# Receiver.net
KiCad netlist of a schematic drawn in EAGLE
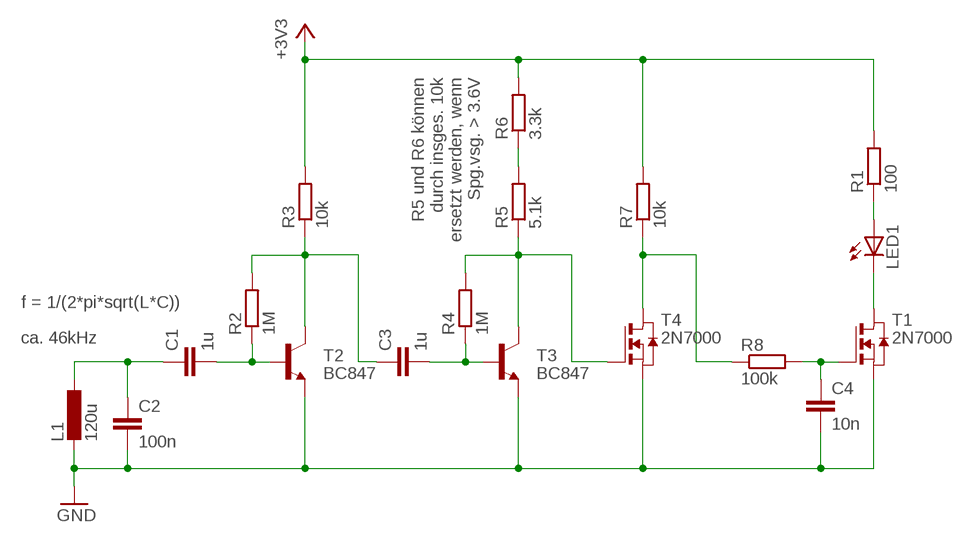
[diagram p0: schematic, sheet 1]

(export (version "E")
  (design (tool "Eeschema 10.0.6"))
  (components
    (comp (ref "C1")
      (value "1u")
      (footprint "eagle-import:C0603")
      (libsource (lib "eagle-import") (part "C-EUC0603"))
    )
    (comp (ref "C2")
      (value "100n")
      (footprint "eagle-import:C0603")
      (libsource (lib "eagle-import") (part "C-EUC0603"))
    )
    (comp (ref "C3")
      (value "1u")
      (footprint "eagle-import:C0603")
      (libsource (lib "eagle-import") (part "C-EUC0603"))
    )
    (comp (ref "C4")
      (value "10n")
      (footprint "eagle-import:C0603")
      (libsource (lib "eagle-import") (part "C-EUC0603"))
    )
    (comp (ref "L1")
      (value "120u")
      (footprint "eagle-import:L1812")
      (libsource (lib "eagle-import") (part "L-EUL1812"))
    )
    (comp (ref "LED1")
      (value "LEDCHIPLED_0603")
      (footprint "eagle-import:CHIPLED_0603")
      (libsource (lib "eagle-import") (part "LEDCHIPLED_0603"))
    )
    (comp (ref "R1")
      (value "100")
      (footprint "eagle-import:R0603")
      (libsource (lib "eagle-import") (part "R-EU_R0603"))
    )
    (comp (ref "R2")
      (value "1M")
      (footprint "eagle-import:R0603")
      (libsource (lib "eagle-import") (part "R-EU_R0603"))
    )
    (comp (ref "R3")
      (value "10k")
      (footprint "eagle-import:R0603")
      (libsource (lib "eagle-import") (part "R-EU_R0603"))
    )
    (comp (ref "R4")
      (value "1M")
      (footprint "eagle-import:R0603")
      (libsource (lib "eagle-import") (part "R-EU_R0603"))
    )
    (comp (ref "R5")
      (value "5.1k")
      (footprint "eagle-import:R0603")
      (libsource (lib "eagle-import") (part "R-EU_R0603"))
    )
    (comp (ref "R6")
      (value "3.3k")
      (footprint "eagle-import:R0603")
      (libsource (lib "eagle-import") (part "R-EU_R0603"))
    )
    (comp (ref "R7")
      (value "10k")
      (footprint "eagle-import:R0603")
      (libsource (lib "eagle-import") (part "R-EU_R0603"))
    )
    (comp (ref "R8")
      (value "100k")
      (footprint "eagle-import:R0603")
      (libsource (lib "eagle-import") (part "R-EU_R0603"))
    )
    (comp (ref "T1")
      (value "2N7000")
      (footprint "eagle-import:SOT-23")
      (libsource (lib "eagle-import") (part "NMOSSOT23"))
    )
    (comp (ref "T2")
      (value "BC847")
      (footprint "eagle-import:SOT23")
      (libsource (lib "eagle-import") (part "BC847"))
    )
    (comp (ref "T3")
      (value "BC847")
      (footprint "eagle-import:SOT23")
      (libsource (lib "eagle-import") (part "BC847"))
    )
    (comp (ref "T4")
      (value "2N7000")
      (footprint "eagle-import:SOT-23")
      (libsource (lib "eagle-import") (part "NMOSSOT23"))
    )
  )
  (nets
    (net (code "1") (name "+3V3") (class "Default")
      (node (ref "R1") (pin "2") (pinfunction "2_2") (pintype "passive"))
      (node (ref "R3") (pin "2") (pinfunction "2_2") (pintype "passive"))
      (node (ref "R6") (pin "2") (pinfunction "2_2") (pintype "passive"))
      (node (ref "R7") (pin "2") (pinfunction "2_2") (pintype "passive"))
    )
    (net (code "2") (name "GND") (class "Default")
      (node (ref "C2") (pin "2") (pinfunction "2_2") (pintype "passive"))
      (node (ref "C4") (pin "2") (pinfunction "2_2") (pintype "passive"))
      (node (ref "L1") (pin "2") (pinfunction "2_2") (pintype "passive"))
      (node (ref "T1") (pin "2") (pinfunction "S_2") (pintype "passive"))
      (node (ref "T2") (pin "2") (pinfunction "E_2") (pintype "passive"))
      (node (ref "T3") (pin "2") (pinfunction "E_2") (pintype "passive"))
      (node (ref "T4") (pin "2") (pinfunction "S_2") (pintype "passive"))
    )
    (net (code "3") (name "Net-(C1-Pad1)") (class "Default")
      (node (ref "C1") (pin "1") (pinfunction "1_1") (pintype "passive"))
      (node (ref "C2") (pin "1") (pinfunction "1_1") (pintype "passive"))
      (node (ref "L1") (pin "1") (pinfunction "1_1") (pintype "passive"))
    )
    (net (code "4") (name "Net-(LED1-PadA)") (class "Default")
      (node (ref "LED1") (pin "A") (pinfunction "A_A") (pintype "passive"))
      (node (ref "R1") (pin "1") (pinfunction "1_1") (pintype "passive"))
    )
    (net (code "5") (name "Net-(R5-Pad2)") (class "Default")
      (node (ref "R5") (pin "2") (pinfunction "2_2") (pintype "passive"))
      (node (ref "R6") (pin "1") (pinfunction "1_1") (pintype "passive"))
    )
    (net (code "6") (name "Net-(T1-D)") (class "Default")
      (node (ref "LED1") (pin "C") (pinfunction "C_C") (pintype "passive"))
      (node (ref "T1") (pin "1") (pinfunction "D_1") (pintype "passive"))
    )
    (net (code "7") (name "Net-(T1-G)") (class "Default")
      (node (ref "C4") (pin "1") (pinfunction "1_1") (pintype "passive"))
      (node (ref "R8") (pin "2") (pinfunction "2_2") (pintype "passive"))
      (node (ref "T1") (pin "3") (pinfunction "G_3") (pintype "passive"))
    )
    (net (code "8") (name "Net-(T2-B)") (class "Default")
      (node (ref "C1") (pin "2") (pinfunction "2_2") (pintype "passive"))
      (node (ref "R2") (pin "1") (pinfunction "1_1") (pintype "passive"))
      (node (ref "T2") (pin "1") (pinfunction "B_1") (pintype "passive"))
    )
    (net (code "9") (name "Net-(T2-C)") (class "Default")
      (node (ref "C3") (pin "1") (pinfunction "1_1") (pintype "passive"))
      (node (ref "R2") (pin "2") (pinfunction "2_2") (pintype "passive"))
      (node (ref "R3") (pin "1") (pinfunction "1_1") (pintype "passive"))
      (node (ref "T2") (pin "3") (pinfunction "C_3") (pintype "passive"))
    )
    (net (code "10") (name "Net-(T3-B)") (class "Default")
      (node (ref "C3") (pin "2") (pinfunction "2_2") (pintype "passive"))
      (node (ref "R4") (pin "1") (pinfunction "1_1") (pintype "passive"))
      (node (ref "T3") (pin "1") (pinfunction "B_1") (pintype "passive"))
    )
    (net (code "11") (name "Net-(T3-C)") (class "Default")
      (node (ref "R4") (pin "2") (pinfunction "2_2") (pintype "passive"))
      (node (ref "R5") (pin "1") (pinfunction "1_1") (pintype "passive"))
      (node (ref "T3") (pin "3") (pinfunction "C_3") (pintype "passive"))
      (node (ref "T4") (pin "3") (pinfunction "G_3") (pintype "passive"))
    )
    (net (code "12") (name "Net-(T4-D)") (class "Default")
      (node (ref "R7") (pin "1") (pinfunction "1_1") (pintype "passive"))
      (node (ref "R8") (pin "1") (pinfunction "1_1") (pintype "passive"))
      (node (ref "T4") (pin "1") (pinfunction "D_1") (pintype "passive"))
    )
  )
)
